# expansion_can_rev_B.net
KiCad netlist of a schematic drawn in EAGLE
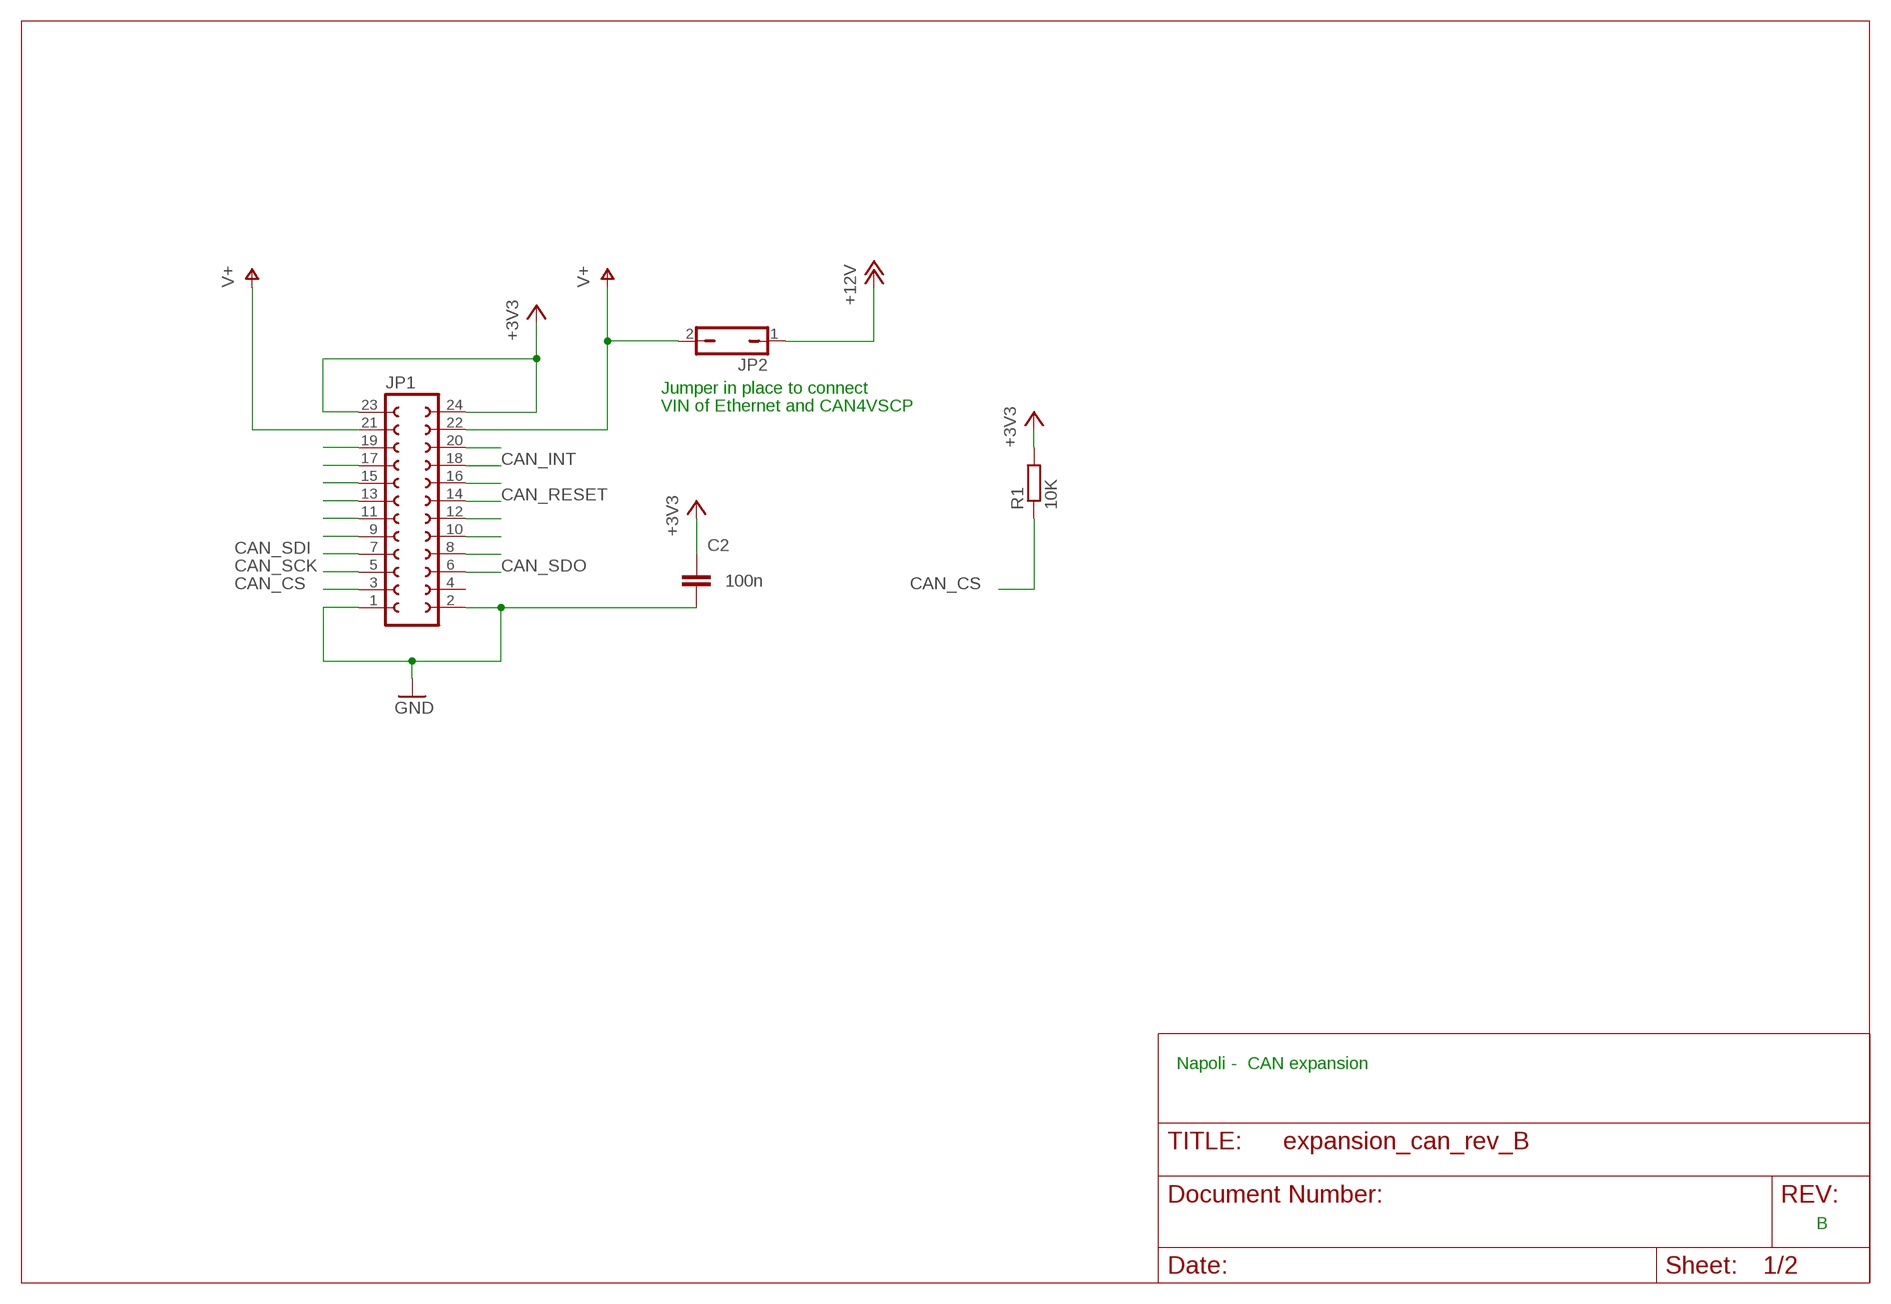
[diagram p0: schematic, sheet 1]
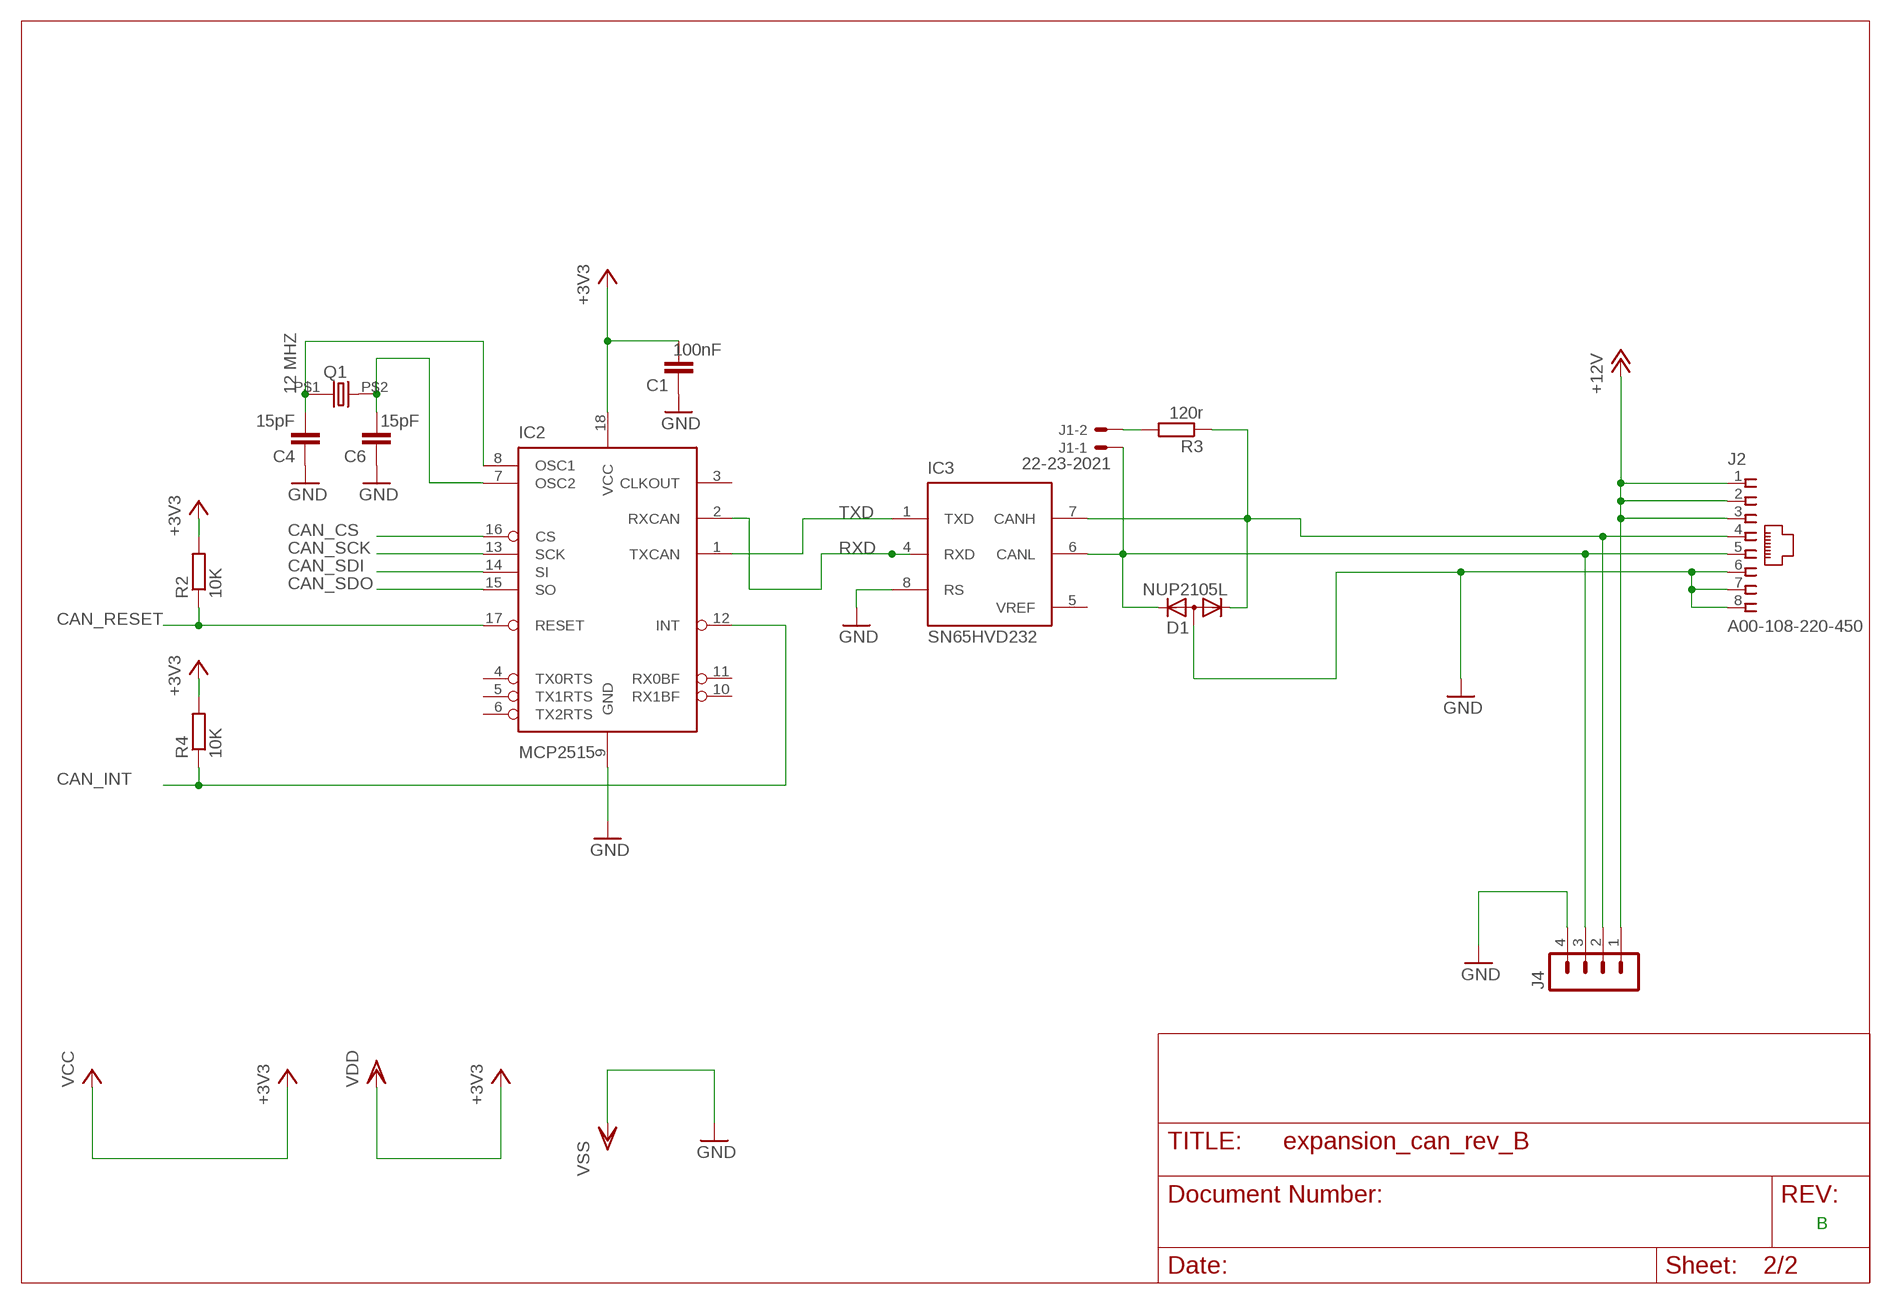
[diagram p1: schematic, sheet 2]

(export (version "E")
  (design (tool "Eeschema 10.0.6"))
  (components
    (comp (ref "C2")
      (value "100n")
      (footprint "eagle-import:C0805")
      (libsource (lib "eagle-import") (part "C-EUC0805"))
    )
    (comp (ref "JP1")
      (value "FE12-2")
      (footprint "eagle-import:FE12-2")
      (libsource (lib "eagle-import") (part "FE12-2"))
    )
    (comp (ref "JP2")
      (value "JP1Q")
      (footprint "eagle-import:JP1")
      (libsource (lib "eagle-import") (part "JP1Q"))
    )
    (comp (ref "R1")
      (value "10K")
      (footprint "eagle-import:R0805")
      (libsource (lib "eagle-import") (part "R-EU_R0805"))
    )
    (comp (ref "C1")
      (value "100nF")
      (footprint "eagle-import:C0805")
      (libsource (lib "eagle-import") (part "C-EUC0805"))
    )
    (comp (ref "C4")
      (value "15pF")
      (footprint "eagle-import:C0805")
      (libsource (lib "eagle-import") (part "C-EUC0805"))
    )
    (comp (ref "C6")
      (value "15pF")
      (footprint "eagle-import:C0805")
      (libsource (lib "eagle-import") (part "C-EUC0805"))
    )
    (comp (ref "D1")
      (value "NUP2105L")
      (footprint "eagle-import:SOT23")
      (libsource (lib "eagle-import") (part "DIODE-2CA|ACSOT23"))
    )
    (comp (ref "IC2")
      (value "MCP2515")
      (footprint "eagle-import:SO-18W")
      (libsource (lib "eagle-import") (part "MCP2515"))
    )
    (comp (ref "IC3")
      (value "SN65HVD232")
      (footprint "eagle-import:SO-08")
      (libsource (lib "eagle-import") (part "MCP2551SN"))
    )
    (comp (ref "J1")
      (value "22-23-2021")
      (footprint "eagle-import:22-23-2021")
      (fields (field (name "MF") "MOLEX"))
      (libsource (lib "eagle-import") (part "22-23-2021"))
    )
    (comp (ref "J2")
      (value "A00-108-220-450")
      (footprint "eagle-import:RJ-45")
      (libsource (lib "eagle-import") (part "A00-108-220-450"))
    )
    (comp (ref "J4")
      (value "MA04-1")
      (footprint "eagle-import:MA04-1")
      (libsource (lib "eagle-import") (part "MA04-1"))
    )
    (comp (ref "Q1")
      (value "12 MHZ")
      (footprint "eagle-import:9C")
      (libsource (lib "eagle-import") (part "HC-49S"))
    )
    (comp (ref "R2")
      (value "10K")
      (footprint "eagle-import:R0805")
      (libsource (lib "eagle-import") (part "R-EU_R0805"))
    )
    (comp (ref "R3")
      (value "120r")
      (footprint "eagle-import:R0805")
      (libsource (lib "eagle-import") (part "R-EU_R0805"))
    )
    (comp (ref "R4")
      (value "10K")
      (footprint "eagle-import:R0805")
      (libsource (lib "eagle-import") (part "R-EU_R0805"))
    )
  )
  (nets
    (net (code "1") (name "+3V3") (class "Default")
      (node (ref "C1") (pin "2") (pinfunction "2_2") (pintype "passive"))
      (node (ref "C2") (pin "1") (pinfunction "1_1") (pintype "passive"))
      (node (ref "IC2") (pin "18") (pinfunction "VCC_18") (pintype "power_in"))
      (node (ref "JP1") (pin "23") (pinfunction "23_23") (pintype "passive"))
      (node (ref "JP1") (pin "24") (pinfunction "24_24") (pintype "passive"))
      (node (ref "R1") (pin "2") (pinfunction "2_2") (pintype "passive"))
      (node (ref "R2") (pin "2") (pinfunction "2_2") (pintype "passive"))
      (node (ref "R4") (pin "2") (pinfunction "2_2") (pintype "passive"))
    )
    (net (code "2") (name "+12V") (class "Default")
      (node (ref "J2") (pin "1") (pinfunction "1_1") (pintype "passive"))
      (node (ref "J2") (pin "2") (pinfunction "2_2") (pintype "passive"))
      (node (ref "J2") (pin "3") (pinfunction "3_3") (pintype "passive"))
      (node (ref "J4") (pin "1") (pinfunction "1_1") (pintype "passive"))
      (node (ref "JP2") (pin "1") (pinfunction "1_1") (pintype "passive"))
    )
    (net (code "3") (name "CAN_CS") (class "Default")
      (node (ref "IC2") (pin "16") (pinfunction "CS_16") (pintype "input"))
      (node (ref "JP1") (pin "3") (pinfunction "3_3") (pintype "passive"))
      (node (ref "R1") (pin "1") (pinfunction "1_1") (pintype "passive"))
    )
    (net (code "4") (name "CAN_INT") (class "Default")
      (node (ref "IC2") (pin "12") (pinfunction "INT_12") (pintype "output"))
      (node (ref "JP1") (pin "18") (pinfunction "18_18") (pintype "passive"))
      (node (ref "R4") (pin "1") (pinfunction "1_1") (pintype "passive"))
    )
    (net (code "5") (name "CAN_RESET") (class "Default")
      (node (ref "IC2") (pin "17") (pinfunction "RESET_17") (pintype "input"))
      (node (ref "JP1") (pin "14") (pinfunction "14_14") (pintype "passive"))
      (node (ref "R2") (pin "1") (pinfunction "1_1") (pintype "passive"))
    )
    (net (code "6") (name "CAN_SCK") (class "Default")
      (node (ref "IC2") (pin "13") (pinfunction "SCK_13") (pintype "input"))
      (node (ref "JP1") (pin "5") (pinfunction "5_5") (pintype "passive"))
    )
    (net (code "7") (name "CAN_SDI") (class "Default")
      (node (ref "IC2") (pin "14") (pinfunction "SI_14") (pintype "input"))
      (node (ref "JP1") (pin "7") (pinfunction "7_7") (pintype "passive"))
    )
    (net (code "8") (name "CAN_SDO") (class "Default")
      (node (ref "IC2") (pin "15") (pinfunction "SO_15") (pintype "output"))
      (node (ref "JP1") (pin "6") (pinfunction "6_6") (pintype "passive"))
    )
    (net (code "9") (name "GND") (class "Default")
      (node (ref "C1") (pin "1") (pinfunction "1_1") (pintype "passive"))
      (node (ref "C2") (pin "2") (pinfunction "2_2") (pintype "passive"))
      (node (ref "C4") (pin "1") (pinfunction "1_1") (pintype "passive"))
      (node (ref "C6") (pin "1") (pinfunction "1_1") (pintype "passive"))
      (node (ref "D1") (pin "3") (pinfunction "A_3") (pintype "passive"))
      (node (ref "IC2") (pin "9") (pinfunction "GND_9") (pintype "power_in"))
      (node (ref "IC3") (pin "8") (pinfunction "RS_8") (pintype "input"))
      (node (ref "J2") (pin "6") (pinfunction "6_6") (pintype "passive"))
      (node (ref "J2") (pin "7") (pinfunction "7_7") (pintype "passive"))
      (node (ref "J2") (pin "8") (pinfunction "8_8") (pintype "passive"))
      (node (ref "J4") (pin "4") (pinfunction "4_4") (pintype "passive"))
      (node (ref "JP1") (pin "1") (pinfunction "1_1") (pintype "passive"))
      (node (ref "JP1") (pin "2") (pinfunction "2_2") (pintype "passive"))
    )
    (net (code "10") (name "Net-(D1-K1)") (class "Default")
      (node (ref "D1") (pin "1") (pinfunction "K1_1") (pintype "passive"))
      (node (ref "IC3") (pin "7") (pinfunction "CANH_7") (pintype "bidirectional"))
      (node (ref "J2") (pin "4") (pinfunction "4_4") (pintype "passive"))
      (node (ref "J4") (pin "2") (pinfunction "2_2") (pintype "passive"))
      (node (ref "R3") (pin "1") (pinfunction "1_1") (pintype "passive"))
    )
    (net (code "11") (name "Net-(D1-K2)") (class "Default")
      (node (ref "D1") (pin "2") (pinfunction "K2_2") (pintype "passive"))
      (node (ref "IC3") (pin "6") (pinfunction "CANL_6") (pintype "bidirectional"))
      (node (ref "J1") (pin "1") (pinfunction "S_1") (pintype "passive"))
      (node (ref "J2") (pin "5") (pinfunction "5_5") (pintype "passive"))
      (node (ref "J4") (pin "3") (pinfunction "3_3") (pintype "passive"))
    )
    (net (code "12") (name "Net-(IC2-OSC1)") (class "Default")
      (node (ref "C4") (pin "2") (pinfunction "2_2") (pintype "passive"))
      (node (ref "IC2") (pin "8") (pinfunction "OSC1_8") (pintype "input"))
      (node (ref "Q1") (pin "P$1") (pinfunction "1_P$1") (pintype "passive"))
    )
    (net (code "13") (name "Net-(IC2-OSC2)") (class "Default")
      (node (ref "C6") (pin "2") (pinfunction "2_2") (pintype "passive"))
      (node (ref "IC2") (pin "7") (pinfunction "OSC2_7") (pintype "output"))
      (node (ref "Q1") (pin "P$2") (pinfunction "2_P$2") (pintype "passive"))
    )
    (net (code "14") (name "Net-(J1B-S)") (class "Default")
      (node (ref "J1") (pin "2") (pinfunction "S_2") (pintype "passive"))
      (node (ref "R3") (pin "2") (pinfunction "2_2") (pintype "passive"))
    )
    (net (code "15") (name "RXD") (class "Default")
      (node (ref "IC2") (pin "2") (pinfunction "RXCAN_2") (pintype "input"))
      (node (ref "IC3") (pin "4") (pinfunction "RXD_4") (pintype "output"))
    )
    (net (code "16") (name "TXD") (class "Default")
      (node (ref "IC2") (pin "1") (pinfunction "TXCAN_1") (pintype "output"))
      (node (ref "IC3") (pin "1") (pinfunction "TXD_1") (pintype "input"))
    )
    (net (code "17") (name "V+") (class "Default")
      (node (ref "JP1") (pin "21") (pinfunction "21_21") (pintype "passive"))
      (node (ref "JP1") (pin "22") (pinfunction "22_22") (pintype "passive"))
      (node (ref "JP2") (pin "2") (pinfunction "2_2") (pintype "passive"))
    )
    (net (code "18") (name "VREF") (class "Default")
      (node (ref "IC3") (pin "5") (pinfunction "VREF_5") (pintype "power_in"))
    )
    (net (code "19") (name "unconnected-(IC2-CLKOUT-Pad3)") (class "Default")
      (node (ref "IC2") (pin "3") (pinfunction "CLKOUT_3") (pintype "output"))
    )
    (net (code "20") (name "unconnected-(IC2-RX0BF-Pad11)") (class "Default")
      (node (ref "IC2") (pin "11") (pinfunction "RX0BF_11") (pintype "output"))
    )
    (net (code "21") (name "unconnected-(IC2-RX1BF-Pad10)") (class "Default")
      (node (ref "IC2") (pin "10") (pinfunction "RX1BF_10") (pintype "output"))
    )
    (net (code "22") (name "unconnected-(IC2-TX0RTS-Pad4)") (class "Default")
      (node (ref "IC2") (pin "4") (pinfunction "TX0RTS_4") (pintype "input"))
    )
    (net (code "23") (name "unconnected-(IC2-TX1RTS-Pad5)") (class "Default")
      (node (ref "IC2") (pin "5") (pinfunction "TX1RTS_5") (pintype "input"))
    )
    (net (code "24") (name "unconnected-(IC2-TX2RTS-Pad6)") (class "Default")
      (node (ref "IC2") (pin "6") (pinfunction "TX2RTS_6") (pintype "input"))
    )
    (net (code "25") (name "unconnected-(JP1-Pad4)") (class "Default")
      (node (ref "JP1") (pin "4") (pinfunction "4_4") (pintype "passive"))
    )
    (net (code "26") (name "unconnected-(JP1-Pad8)") (class "Default")
      (node (ref "JP1") (pin "8") (pinfunction "8_8") (pintype "passive"))
    )
    (net (code "27") (name "unconnected-(JP1-Pad9)") (class "Default")
      (node (ref "JP1") (pin "9") (pinfunction "9_9") (pintype "passive"))
    )
    (net (code "28") (name "unconnected-(JP1-Pad10)") (class "Default")
      (node (ref "JP1") (pin "10") (pinfunction "10_10") (pintype "passive"))
    )
    (net (code "29") (name "unconnected-(JP1-Pad11)") (class "Default")
      (node (ref "JP1") (pin "11") (pinfunction "11_11") (pintype "passive"))
    )
    (net (code "30") (name "unconnected-(JP1-Pad12)") (class "Default")
      (node (ref "JP1") (pin "12") (pinfunction "12_12") (pintype "passive"))
    )
    (net (code "31") (name "unconnected-(JP1-Pad13)") (class "Default")
      (node (ref "JP1") (pin "13") (pinfunction "13_13") (pintype "passive"))
    )
    (net (code "32") (name "unconnected-(JP1-Pad15)") (class "Default")
      (node (ref "JP1") (pin "15") (pinfunction "15_15") (pintype "passive"))
    )
    (net (code "33") (name "unconnected-(JP1-Pad16)") (class "Default")
      (node (ref "JP1") (pin "16") (pinfunction "16_16") (pintype "passive"))
    )
    (net (code "34") (name "unconnected-(JP1-Pad17)") (class "Default")
      (node (ref "JP1") (pin "17") (pinfunction "17_17") (pintype "passive"))
    )
    (net (code "35") (name "unconnected-(JP1-Pad19)") (class "Default")
      (node (ref "JP1") (pin "19") (pinfunction "19_19") (pintype "passive"))
    )
    (net (code "36") (name "unconnected-(JP1-Pad20)") (class "Default")
      (node (ref "JP1") (pin "20") (pinfunction "20_20") (pintype "passive"))
    )
  )
)
